# cloak.net
KiCad netlist of a schematic drawn in EAGLE
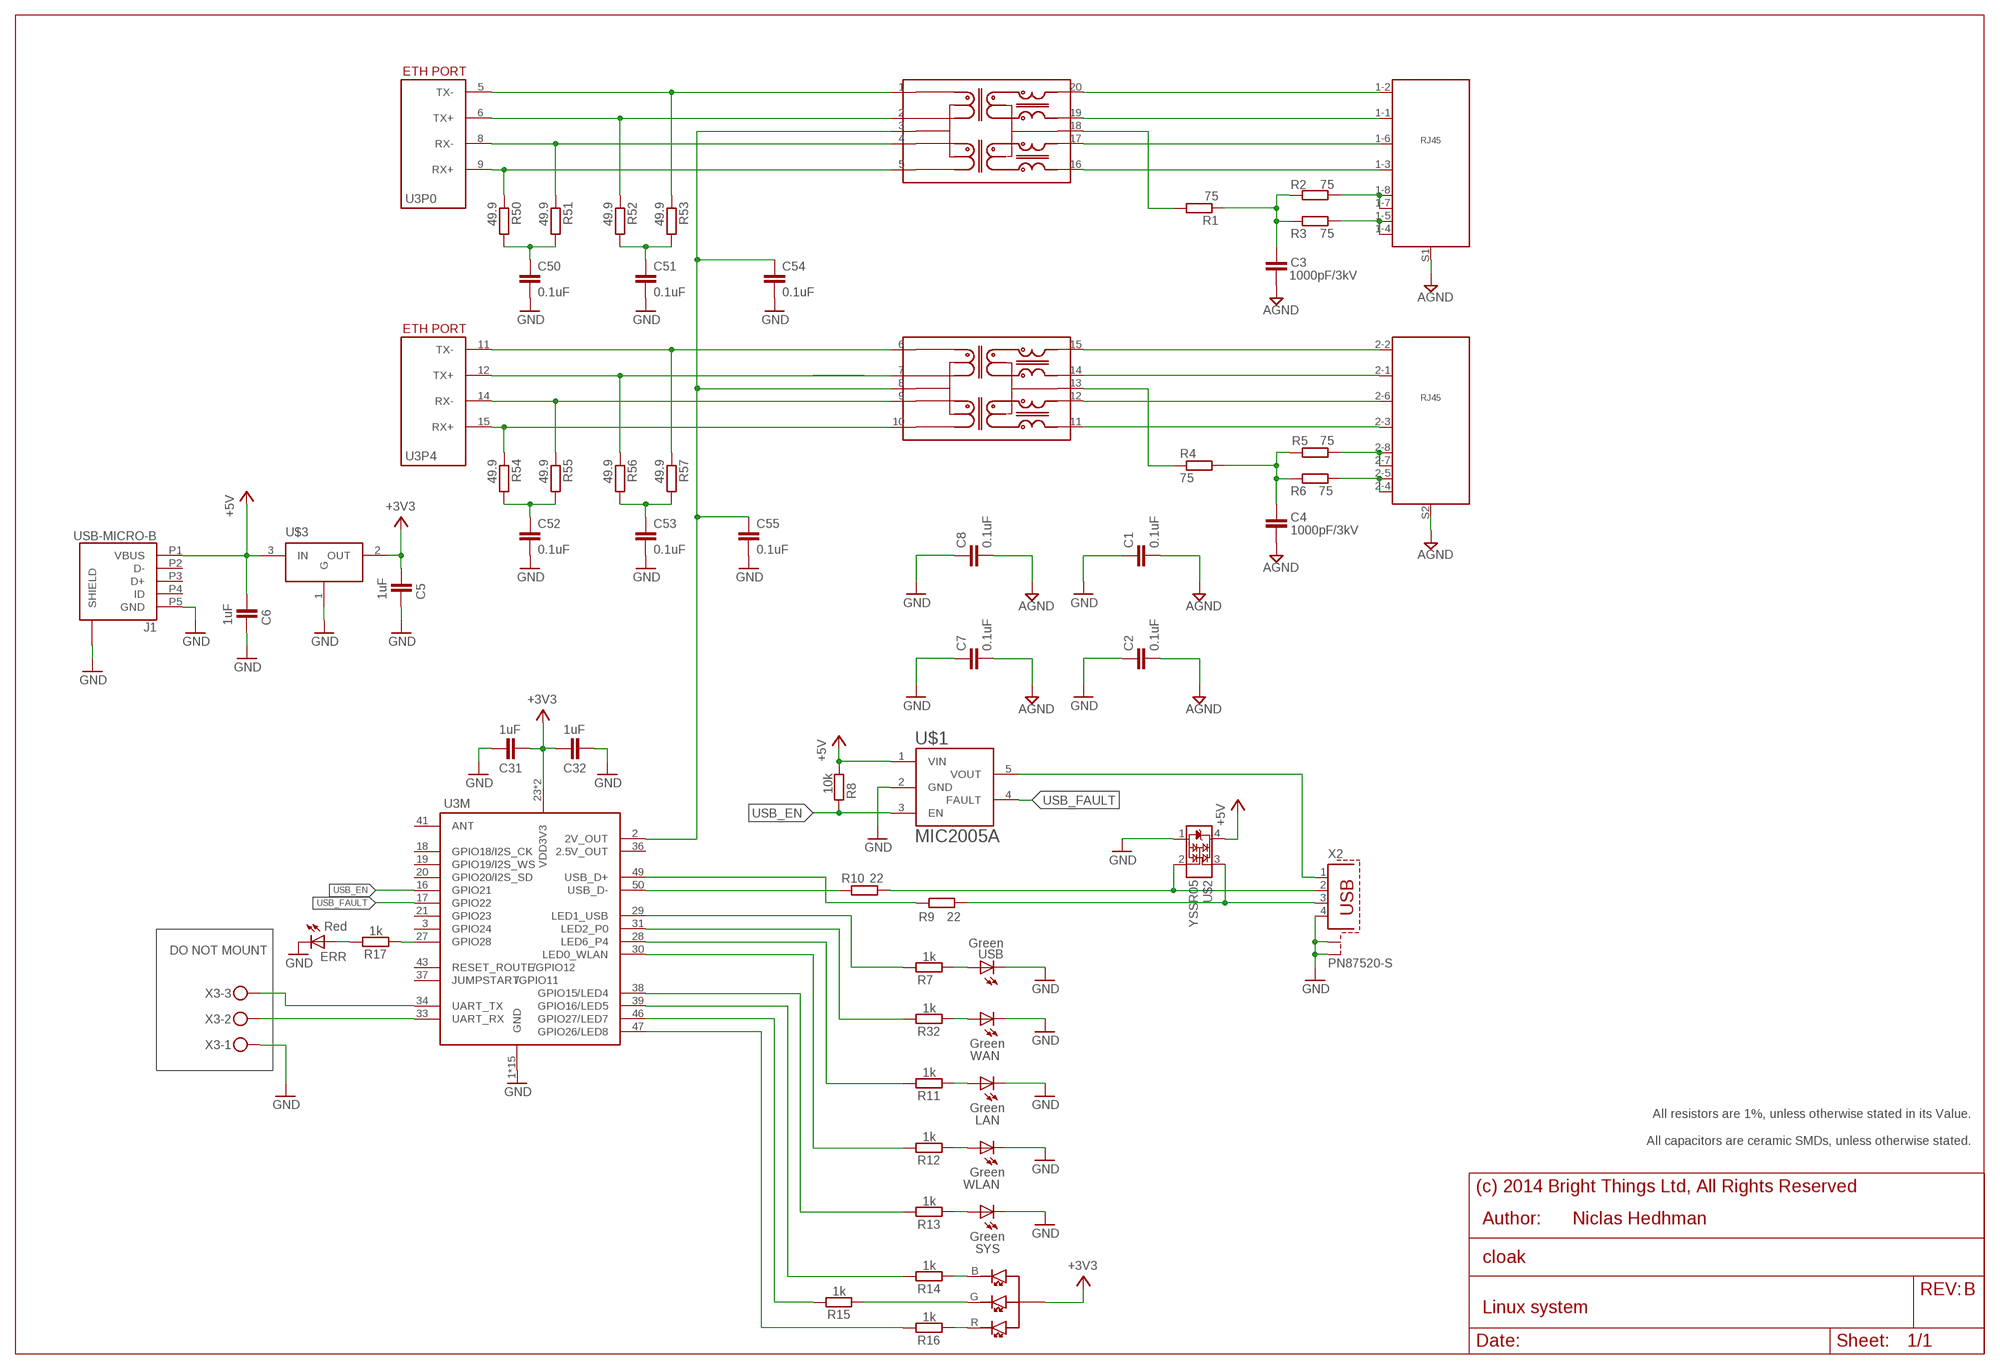
[diagram p0: schematic, sheet 1]

(export (version "E")
  (design (tool "Eeschema 10.0.6"))
  (components
    (comp (ref "C1")
      (value "0.1uF")
      (footprint "eagle-import:C0603")
      (fields (field (name "MANUFACTURER") "Kemet") (field (name "PARTNO") "C0603C104K5RAC7411"))
      (libsource (lib "eagle-import") (part "C-EUC0603"))
    )
    (comp (ref "C2")
      (value "0.1uF")
      (footprint "eagle-import:C0603")
      (fields (field (name "MANUFACTURER") "Kemet") (field (name "PARTNO") "C0603C104K5RAC7411"))
      (libsource (lib "eagle-import") (part "C-EUC0603"))
    )
    (comp (ref "C3")
      (value "1000pF/3kV")
      (footprint "eagle-import:C1808")
      (fields (field (name "MANUFACTURER") "Kemet") (field (name "PARTNO") "C1808C102KHRACTU"))
      (libsource (lib "eagle-import") (part "C-EUC1808"))
    )
    (comp (ref "C4")
      (value "1000pF/3kV")
      (footprint "eagle-import:C1808")
      (fields (field (name "MANUFACTURER") "Kemet") (field (name "PARTNO") "C1808C102KHRACTU"))
      (libsource (lib "eagle-import") (part "C-EUC1808"))
    )
    (comp (ref "C5")
      (value "1uF")
      (footprint "eagle-import:C0603")
      (fields (field (name "MF") "Kemet") (field (name "MPN") "C0603C105K8PACTU"))
      (libsource (lib "eagle-import") (part "C-EUC0603"))
    )
    (comp (ref "C6")
      (value "1uF")
      (footprint "eagle-import:C0603")
      (fields (field (name "MF") "Kemet") (field (name "MPN") "C0603C105K8PACTU"))
      (libsource (lib "eagle-import") (part "C-EUC0603"))
    )
    (comp (ref "C7")
      (value "0.1uF")
      (footprint "eagle-import:C0603")
      (fields (field (name "MANUFACTURER") "Kemet") (field (name "PARTNO") "C0603C104K5RAC7411"))
      (libsource (lib "eagle-import") (part "C-EUC0603"))
    )
    (comp (ref "C8")
      (value "0.1uF")
      (footprint "eagle-import:C0603")
      (fields (field (name "MANUFACTURER") "Kemet") (field (name "PARTNO") "C0603C104K5RAC7411"))
      (libsource (lib "eagle-import") (part "C-EUC0603"))
    )
    (comp (ref "C31")
      (value "1uF")
      (footprint "eagle-import:C0603")
      (fields (field (name "MF") "Kemet") (field (name "MPN") "C0603C105K8PACTU"))
      (libsource (lib "eagle-import") (part "C-EUC0603"))
    )
    (comp (ref "C32")
      (value "1uF")
      (footprint "eagle-import:C0603")
      (fields (field (name "MF") "Kemet") (field (name "MPN") "C0603C105K8PACTU"))
      (libsource (lib "eagle-import") (part "C-EUC0603"))
    )
    (comp (ref "C50")
      (value "0.1uF")
      (footprint "eagle-import:C0603")
      (fields (field (name "MF") "Kemet") (field (name "MPN") "C0603C104K5RAC7411"))
      (libsource (lib "eagle-import") (part "C-EUC0603"))
    )
    (comp (ref "C51")
      (value "0.1uF")
      (footprint "eagle-import:C0603")
      (fields (field (name "MF") "Kemet") (field (name "MPN") "C0603C104K5RAC7411"))
      (libsource (lib "eagle-import") (part "C-EUC0603"))
    )
    (comp (ref "C52")
      (value "0.1uF")
      (footprint "eagle-import:C0603")
      (fields (field (name "MF") "Kemet") (field (name "MPN") "C0603C104K5RAC7411"))
      (libsource (lib "eagle-import") (part "C-EUC0603"))
    )
    (comp (ref "C53")
      (value "0.1uF")
      (footprint "eagle-import:C0603")
      (fields (field (name "MF") "Kemet") (field (name "MPN") "C0603C104K5RAC7411"))
      (libsource (lib "eagle-import") (part "C-EUC0603"))
    )
    (comp (ref "C54")
      (value "0.1uF")
      (footprint "eagle-import:C0603")
      (fields (field (name "MF") "Kemet") (field (name "MPN") "C0603C104K5RAC7411"))
      (libsource (lib "eagle-import") (part "C-EUC0603"))
    )
    (comp (ref "C55")
      (value "0.1uF")
      (footprint "eagle-import:C0603")
      (fields (field (name "MF") "Kemet") (field (name "MPN") "C0603C104K5RAC7411"))
      (libsource (lib "eagle-import") (part "C-EUC0603"))
    )
    (comp (ref "CLOAK")
      (value "LTST-C19FD1WT")
      (footprint "eagle-import:LTST-C19FD1WT")
      (fields (field (name "MF") "Lite-On Inc"))
      (libsource (lib "eagle-import") (part "LTST-C19FD1WT"))
    )
    (comp (ref "ERR")
      (value "Red")
      (footprint "eagle-import:CHIP-LED0603")
      (fields (field (name "MF") "OSRAM Opto Semiconductors Inc") (field (name "MPN") "LG Q971-KN-1"))
      (libsource (lib "eagle-import") (part "LEDCHIP-LED0603"))
    )
    (comp (ref "J1")
      (value "USB-MICRO-B")
      (footprint "eagle-import:CON2_USB_MICRO_B_AT")
      (libsource (lib "eagle-import") (part "USB-MICRO-B"))
    )
    (comp (ref "LAN")
      (value "Green")
      (footprint "eagle-import:CHIP-LED0603")
      (fields (field (name "MF") "OSRAM Opto Semiconductors Inc") (field (name "MPN") "LG Q971-KN-1"))
      (libsource (lib "eagle-import") (part "LEDCHIP-LED0603"))
    )
    (comp (ref "P4")
      (value "ETHERNET_2PORT")
      (footprint "eagle-import:SJA-1X2")
      (libsource (lib "eagle-import") (part "ETHERNET_2PORT"))
    )
    (comp (ref "R1")
      (value "75")
      (footprint "eagle-import:R0805")
      (fields (field (name "MANUFACTURER") "Vishay Dale") (field (name "PARTNO") "CRCW060375R0FKEA"))
      (libsource (lib "eagle-import") (part "resistor_R-EU_R0805"))
    )
    (comp (ref "R2")
      (value "75")
      (footprint "eagle-import:R0805")
      (fields (field (name "MANUFACTURER") "Vishay Dale") (field (name "PARTNO") "CRCW060375R0FKEA"))
      (libsource (lib "eagle-import") (part "resistor_R-EU_R0805"))
    )
    (comp (ref "R3")
      (value "75")
      (footprint "eagle-import:R0805")
      (fields (field (name "MANUFACTURER") "Vishay Dale") (field (name "PARTNO") "CRCW060375R0FKEA"))
      (libsource (lib "eagle-import") (part "resistor_R-EU_R0805"))
    )
    (comp (ref "R4")
      (value "75")
      (footprint "eagle-import:R0805")
      (fields (field (name "MANUFACTURER") "Vishay Dale") (field (name "PARTNO") "CRCW060375R0FKEA"))
      (libsource (lib "eagle-import") (part "resistor_R-EU_R0805"))
    )
    (comp (ref "R5")
      (value "75")
      (footprint "eagle-import:R0805")
      (fields (field (name "MANUFACTURER") "Vishay Dale") (field (name "PARTNO") "CRCW060375R0FKEA"))
      (libsource (lib "eagle-import") (part "resistor_R-EU_R0805"))
    )
    (comp (ref "R6")
      (value "75")
      (footprint "eagle-import:R0805")
      (fields (field (name "MANUFACTURER") "Vishay Dale") (field (name "PARTNO") "CRCW060375R0FKEA"))
      (libsource (lib "eagle-import") (part "resistor_R-EU_R0805"))
    )
    (comp (ref "R7")
      (value "1k")
      (footprint "eagle-import:R0603")
      (fields (field (name "MF") "Vishay Dale") (field (name "MPN") "CRCW06031K0JNEA"))
      (libsource (lib "eagle-import") (part "R-EU_R0603"))
    )
    (comp (ref "R8")
      (value "10k")
      (footprint "eagle-import:R0603")
      (fields (field (name "MF") "Vishay Dale"))
      (libsource (lib "eagle-import") (part "R-EU_R0603"))
    )
    (comp (ref "R9")
      (value "22")
      (footprint "eagle-import:R0805")
      (fields (field (name "MANUFACTURER") "Vishay Dale") (field (name "PARTNO") "CRCW060322R0FKEA"))
      (libsource (lib "eagle-import") (part "resistor_R-EU_R0805"))
    )
    (comp (ref "R10")
      (value "22")
      (footprint "eagle-import:R0805")
      (fields (field (name "MANUFACTURER") "Vishay Dale") (field (name "PARTNO") "CRCW060322R0FKEA"))
      (libsource (lib "eagle-import") (part "resistor_R-EU_R0805"))
    )
    (comp (ref "R11")
      (value "1k")
      (footprint "eagle-import:R0603")
      (fields (field (name "MF") "Vishay Dale") (field (name "MPN") "CRCW06031K0JNEA"))
      (libsource (lib "eagle-import") (part "R-EU_R0603"))
    )
    (comp (ref "R12")
      (value "1k")
      (footprint "eagle-import:R0603")
      (fields (field (name "MF") "Vishay Dale") (field (name "MPN") "CRCW06031K0JNEA"))
      (libsource (lib "eagle-import") (part "R-EU_R0603"))
    )
    (comp (ref "R13")
      (value "1k")
      (footprint "eagle-import:R0603")
      (fields (field (name "MF") "Vishay Dale") (field (name "MPN") "CRCW06031K0JNEA"))
      (libsource (lib "eagle-import") (part "R-EU_R0603"))
    )
    (comp (ref "R14")
      (value "1k")
      (footprint "eagle-import:R0603")
      (fields (field (name "MF") "Vishay Dale") (field (name "MPN") "CRCW06031K0JNEA"))
      (libsource (lib "eagle-import") (part "R-EU_R0603"))
    )
    (comp (ref "R15")
      (value "1k")
      (footprint "eagle-import:R0603")
      (fields (field (name "MF") "Vishay Dale") (field (name "MPN") "CRCW06031K0JNEA"))
      (libsource (lib "eagle-import") (part "R-EU_R0603"))
    )
    (comp (ref "R16")
      (value "1k")
      (footprint "eagle-import:R0603")
      (fields (field (name "MF") "Vishay Dale") (field (name "MPN") "CRCW06031K0JNEA"))
      (libsource (lib "eagle-import") (part "R-EU_R0603"))
    )
    (comp (ref "R17")
      (value "1k")
      (footprint "eagle-import:R0603")
      (fields (field (name "MF") "Vishay Dale") (field (name "MPN") "CRCW06031K0JNEA"))
      (libsource (lib "eagle-import") (part "R-EU_R0603"))
    )
    (comp (ref "R32")
      (value "1k")
      (footprint "eagle-import:R0603")
      (fields (field (name "MF") "Vishay Dale") (field (name "MPN") "CRCW06031K0JNEA"))
      (libsource (lib "eagle-import") (part "R-EU_R0603"))
    )
    (comp (ref "R50")
      (value "49.9")
      (footprint "eagle-import:R0805")
      (fields (field (name "MF") "Vishay Dale") (field (name "MPN") "CRCW060349R9FKEA"))
      (libsource (lib "eagle-import") (part "resistor_R-EU_R0805"))
    )
    (comp (ref "R51")
      (value "49.9")
      (footprint "eagle-import:R0805")
      (fields (field (name "MF") "Vishay Dale") (field (name "MPN") "CRCW060349R9FKEA"))
      (libsource (lib "eagle-import") (part "resistor_R-EU_R0805"))
    )
    (comp (ref "R52")
      (value "49.9")
      (footprint "eagle-import:R0805")
      (fields (field (name "MF") "Vishay Dale") (field (name "MPN") "CRCW060349R9FKEA"))
      (libsource (lib "eagle-import") (part "resistor_R-EU_R0805"))
    )
    (comp (ref "R53")
      (value "49.9")
      (footprint "eagle-import:R0805")
      (fields (field (name "MF") "Vishay Dale") (field (name "MPN") "CRCW060349R9FKEA"))
      (libsource (lib "eagle-import") (part "resistor_R-EU_R0805"))
    )
    (comp (ref "R54")
      (value "49.9")
      (footprint "eagle-import:R0805")
      (fields (field (name "MF") "Vishay Dale") (field (name "MPN") "CRCW060349R9FKEA"))
      (libsource (lib "eagle-import") (part "resistor_R-EU_R0805"))
    )
    (comp (ref "R55")
      (value "49.9")
      (footprint "eagle-import:R0805")
      (fields (field (name "MF") "Vishay Dale") (field (name "MPN") "CRCW060349R9FKEA"))
      (libsource (lib "eagle-import") (part "resistor_R-EU_R0805"))
    )
    (comp (ref "R56")
      (value "49.9")
      (footprint "eagle-import:R0805")
      (fields (field (name "MF") "Vishay Dale") (field (name "MPN") "CRCW060349R9FKEA"))
      (libsource (lib "eagle-import") (part "resistor_R-EU_R0805"))
    )
    (comp (ref "R57")
      (value "49.9")
      (footprint "eagle-import:R0805")
      (fields (field (name "MF") "Vishay Dale") (field (name "MPN") "CRCW060349R9FKEA"))
      (libsource (lib "eagle-import") (part "resistor_R-EU_R0805"))
    )
    (comp (ref "SYS")
      (value "Green")
      (footprint "eagle-import:CHIP-LED0603")
      (fields (field (name "MF") "OSRAM Opto Semiconductors Inc") (field (name "MPN") "LG Q971-KN-1"))
      (libsource (lib "eagle-import") (part "LEDCHIP-LED0603"))
    )
    (comp (ref "TR1")
      (value "HST2038DR")
      (footprint "eagle-import:H2038")
      (fields (field (name "SUPPLIER") "Dragino"))
      (libsource (lib "eagle-import") (part "HST2038DR"))
    )
    (comp (ref "U$1")
      (value "MIC2005A")
      (footprint "eagle-import:SOT-23-5")
      (libsource (lib "eagle-import") (part "MIC2005A"))
    )
    (comp (ref "U$2")
      (value "YSSR05")
      (footprint "eagle-import:YSSR05")
      (libsource (lib "eagle-import") (part "YSSR05"))
    )
    (comp (ref "U$3")
      (value "LDO_REGL")
      (footprint "eagle-import:SOT23")
      (fields (field (name "MF") "Diodes Inc") (field (name "MPN") "AP2120N-3.3TRG1"))
      (libsource (lib "eagle-import") (part "LDO_REGL"))
    )
    (comp (ref "U3")
      (value "DRAGINO_HE")
      (footprint "eagle-import:DRAGINO_HE")
      (libsource (lib "eagle-import") (part "DRAGINO_HE"))
    )
    (comp (ref "USB")
      (value "Green")
      (footprint "eagle-import:CHIP-LED0603")
      (fields (field (name "MF") "OSRAM Opto Semiconductors Inc") (field (name "MPN") "LG Q971-KN-1"))
      (libsource (lib "eagle-import") (part "LEDCHIP-LED0603"))
    )
    (comp (ref "WAN")
      (value "Green")
      (footprint "eagle-import:CHIP-LED0603")
      (fields (field (name "MF") "OSRAM Opto Semiconductors Inc") (field (name "MPN") "LG Q971-KN-1"))
      (libsource (lib "eagle-import") (part "LEDCHIP-LED0603"))
    )
    (comp (ref "WLAN")
      (value "Green")
      (footprint "eagle-import:CHIP-LED0603")
      (fields (field (name "MF") "OSRAM Opto Semiconductors Inc") (field (name "MPN") "LG Q971-KN-1"))
      (libsource (lib "eagle-import") (part "LEDCHIP-LED0603"))
    )
    (comp (ref "X2")
      (value "PN87520-S")
      (footprint "eagle-import:PN87520-S")
      (libsource (lib "eagle-import") (part "PN87520-S"))
    )
    (comp (ref "X3")
      (value "MKDSN1,5/3-5,08")
      (footprint "eagle-import:MKDSN1,5_3-5,08")
      (fields (field (name "MPN") "SMKDSN1,5/3-5,08"))
      (libsource (lib "eagle-import") (part "MKDSN1,5/3-5,08"))
    )
  )
  (nets
    (net (code "1") (name "+3V3") (class "Default")
      (node (ref "C31") (pin "1") (pinfunction "1_1") (pintype "passive"))
      (node (ref "C32") (pin "1") (pinfunction "1_1") (pintype "passive"))
      (node (ref "C5") (pin "1") (pinfunction "1_1") (pintype "passive"))
      (node (ref "CLOAK") (pin "A") (pinfunction "A_A") (pintype "passive"))
      (node (ref "U$3") (pin "2") (pinfunction "OUT_2") (pintype "power_in"))
      (node (ref "U3") (pin "23") (pinfunction "VDD3V3_23") (pintype "power_in"))
      (node (ref "U3") (pin "24") (pinfunction "VDD3V3_24") (pintype "power_in"))
    )
    (net (code "2") (name "+5V") (class "Default")
      (node (ref "C6") (pin "1") (pinfunction "1_1") (pintype "passive"))
      (node (ref "J1") (pin "P1") (pinfunction "VBUS_P1") (pintype "power_in"))
      (node (ref "R8") (pin "2") (pinfunction "2_2") (pintype "passive"))
      (node (ref "U$1") (pin "1") (pinfunction "VIN_1") (pintype "power_in"))
      (node (ref "U$2") (pin "4") (pinfunction "+_4") (pintype "passive"))
      (node (ref "U$3") (pin "3") (pinfunction "IN_3") (pintype "power_in"))
    )
    (net (code "3") (name "/2.5V_OUT") (class "Default")
      (node (ref "U3") (pin "36") (pinfunction "2.5V_OUT_36") (pintype "power_in"))
    )
    (net (code "4") (name "AGND") (class "Default")
      (node (ref "C1") (pin "2") (pinfunction "2_2") (pintype "passive"))
      (node (ref "C2") (pin "2") (pinfunction "2_2") (pintype "passive"))
      (node (ref "C3") (pin "2") (pinfunction "2_2") (pintype "passive"))
      (node (ref "C4") (pin "2") (pinfunction "2_2") (pintype "passive"))
      (node (ref "C7") (pin "2") (pinfunction "2_2") (pintype "passive"))
      (node (ref "C8") (pin "2") (pinfunction "2_2") (pintype "passive"))
      (node (ref "P4") (pin "S1") (pinfunction "SHIELD_S1") (pintype "power_in"))
      (node (ref "P4") (pin "S2") (pinfunction "SHIELD_S2") (pintype "power_in"))
    )
    (net (code "5") (name "GND") (class "Default")
      (node (ref "C1") (pin "1") (pinfunction "1_1") (pintype "passive"))
      (node (ref "C2") (pin "1") (pinfunction "1_1") (pintype "passive"))
      (node (ref "C31") (pin "2") (pinfunction "2_2") (pintype "passive"))
      (node (ref "C32") (pin "2") (pinfunction "2_2") (pintype "passive"))
      (node (ref "C5") (pin "2") (pinfunction "2_2") (pintype "passive"))
      (node (ref "C50") (pin "2") (pinfunction "2_2") (pintype "passive"))
      (node (ref "C51") (pin "2") (pinfunction "2_2") (pintype "passive"))
      (node (ref "C52") (pin "2") (pinfunction "2_2") (pintype "passive"))
      (node (ref "C53") (pin "2") (pinfunction "2_2") (pintype "passive"))
      (node (ref "C54") (pin "2") (pinfunction "2_2") (pintype "passive"))
      (node (ref "C55") (pin "2") (pinfunction "2_2") (pintype "passive"))
      (node (ref "C6") (pin "2") (pinfunction "2_2") (pintype "passive"))
      (node (ref "C7") (pin "1") (pinfunction "1_1") (pintype "passive"))
      (node (ref "C8") (pin "1") (pinfunction "1_1") (pintype "passive"))
      (node (ref "ERR") (pin "C") (pinfunction "C_C") (pintype "passive"))
      (node (ref "J1") (pin "P5") (pinfunction "GND_P5") (pintype "passive"))
      (node (ref "J1") (pin "S1") (pinfunction "SHIELD_S1") (pintype "passive"))
      (node (ref "J1") (pin "S2") (pinfunction "SHIELD_S2") (pintype "passive"))
      (node (ref "J1") (pin "S3") (pinfunction "SHIELD_S3") (pintype "passive"))
      (node (ref "J1") (pin "S4") (pinfunction "SHIELD_S4") (pintype "passive"))
      (node (ref "J1") (pin "S5") (pinfunction "SHIELD_S5") (pintype "passive"))
      (node (ref "J1") (pin "S6") (pinfunction "SHIELD_S6") (pintype "passive"))
      (node (ref "LAN") (pin "C") (pinfunction "C_C") (pintype "passive"))
      (node (ref "SYS") (pin "C") (pinfunction "C_C") (pintype "passive"))
      (node (ref "U$1") (pin "2") (pinfunction "GND_2") (pintype "power_in"))
      (node (ref "U$2") (pin "1") (pinfunction "C_1") (pintype "passive"))
      (node (ref "U$3") (pin "1") (pinfunction "G_1") (pintype "power_in"))
      (node (ref "U3") (pin "1") (pinfunction "GND_1") (pintype "power_in"))
      (node (ref "U3") (pin "10") (pinfunction "GND_10") (pintype "power_in"))
      (node (ref "U3") (pin "13") (pinfunction "GND_13") (pintype "power_in"))
      (node (ref "U3") (pin "22") (pinfunction "GND_22") (pintype "power_in"))
      (node (ref "U3") (pin "25") (pinfunction "GND_25") (pintype "power_in"))
      (node (ref "U3") (pin "26") (pinfunction "GND_26") (pintype "power_in"))
      (node (ref "U3") (pin "32") (pinfunction "GND_32") (pintype "power_in"))
      (node (ref "U3") (pin "35") (pinfunction "GND_35") (pintype "power_in"))
      (node (ref "U3") (pin "4") (pinfunction "GND_4") (pintype "power_in"))
      (node (ref "U3") (pin "40") (pinfunction "GND_40") (pintype "power_in"))
      (node (ref "U3") (pin "42") (pinfunction "GND_42") (pintype "power_in"))
      (node (ref "U3") (pin "44") (pinfunction "GND_44") (pintype "power_in"))
      (node (ref "U3") (pin "45") (pinfunction "GND_45") (pintype "power_in"))
      (node (ref "U3") (pin "48") (pinfunction "GND_48") (pintype "power_in"))
      (node (ref "U3") (pin "7") (pinfunction "GND_7") (pintype "power_in"))
      (node (ref "USB") (pin "C") (pinfunction "C_C") (pintype "passive"))
      (node (ref "WAN") (pin "C") (pinfunction "C_C") (pintype "passive"))
      (node (ref "WLAN") (pin "C") (pinfunction "C_C") (pintype "passive"))
      (node (ref "X2") (pin "4") (pinfunction "4_4") (pintype "passive"))
      (node (ref "X2") (pin "S1") (pinfunction "S1_S1") (pintype "passive"))
      (node (ref "X2") (pin "S2") (pinfunction "S2_S2") (pintype "passive"))
      (node (ref "X3") (pin "1") (pinfunction "KL_1") (pintype "passive"))
    )
    (net (code "6") (name "Net-(C3-Pad1)") (class "Default")
      (node (ref "C3") (pin "1") (pinfunction "1_1") (pintype "passive"))
      (node (ref "R1") (pin "1") (pinfunction "1_1") (pintype "passive"))
      (node (ref "R2") (pin "2") (pinfunction "2_2") (pintype "passive"))
      (node (ref "R3") (pin "2") (pinfunction "2_2") (pintype "passive"))
    )
    (net (code "7") (name "Net-(C4-Pad1)") (class "Default")
      (node (ref "C4") (pin "1") (pinfunction "1_1") (pintype "passive"))
      (node (ref "R4") (pin "2") (pinfunction "2_2") (pintype "passive"))
      (node (ref "R5") (pin "2") (pinfunction "2_2") (pintype "passive"))
      (node (ref "R6") (pin "1") (pinfunction "1_1") (pintype "passive"))
    )
    (net (code "8") (name "Net-(C50-Pad1)") (class "Default")
      (node (ref "C50") (pin "1") (pinfunction "1_1") (pintype "passive"))
      (node (ref "R50") (pin "2") (pinfunction "2_2") (pintype "passive"))
      (node (ref "R51") (pin "2") (pinfunction "2_2") (pintype "passive"))
    )
    (net (code "9") (name "Net-(C51-Pad1)") (class "Default")
      (node (ref "C51") (pin "1") (pinfunction "1_1") (pintype "passive"))
      (node (ref "R52") (pin "2") (pinfunction "2_2") (pintype "passive"))
      (node (ref "R53") (pin "2") (pinfunction "2_2") (pintype "passive"))
    )
    (net (code "10") (name "Net-(C52-Pad1)") (class "Default")
      (node (ref "C52") (pin "1") (pinfunction "1_1") (pintype "passive"))
      (node (ref "R54") (pin "2") (pinfunction "2_2") (pintype "passive"))
      (node (ref "R55") (pin "2") (pinfunction "2_2") (pintype "passive"))
    )
    (net (code "11") (name "Net-(C53-Pad1)") (class "Default")
      (node (ref "C53") (pin "1") (pinfunction "1_1") (pintype "passive"))
      (node (ref "R56") (pin "2") (pinfunction "2_2") (pintype "passive"))
      (node (ref "R57") (pin "2") (pinfunction "2_2") (pintype "passive"))
    )
    (net (code "12") (name "Net-(CLOAK-PadB)") (class "Default")
      (node (ref "CLOAK") (pin "B") (pinfunction "B_B") (pintype "passive"))
      (node (ref "R14") (pin "2") (pinfunction "2_2") (pintype "passive"))
    )
    (net (code "13") (name "Net-(CLOAK-PadG)") (class "Default")
      (node (ref "CLOAK") (pin "G") (pinfunction "G_G") (pintype "passive"))
      (node (ref "R15") (pin "2") (pinfunction "2_2") (pintype "passive"))
    )
    (net (code "14") (name "Net-(CLOAK-PadR)") (class "Default")
      (node (ref "CLOAK") (pin "R") (pinfunction "R_R") (pintype "passive"))
      (node (ref "R16") (pin "2") (pinfunction "2_2") (pintype "passive"))
    )
    (net (code "15") (name "Net-(ERR-PadA)") (class "Default")
      (node (ref "ERR") (pin "A") (pinfunction "A_A") (pintype "passive"))
      (node (ref "R17") (pin "1") (pinfunction "1_1") (pintype "passive"))
    )
    (net (code "16") (name "Net-(LAN-PadA)") (class "Default")
      (node (ref "LAN") (pin "A") (pinfunction "A_A") (pintype "passive"))
      (node (ref "R11") (pin "2") (pinfunction "2_2") (pintype "passive"))
    )
    (net (code "17") (name "Net-(P4A-1)") (class "Default")
      (node (ref "P4") (pin "1-1") (pinfunction "1_1-1") (pintype "passive"))
      (node (ref "TR1") (pin "19") (pinfunction "TX-_19") (pintype "passive"))
    )
    (net (code "18") (name "Net-(P4A-2)") (class "Default")
      (node (ref "P4") (pin "1-2") (pinfunction "2_1-2") (pintype "passive"))
      (node (ref "TR1") (pin "20") (pinfunction "TX+_20") (pintype "passive"))
    )
    (net (code "19") (name "Net-(P4A-3)") (class "Default")
      (node (ref "P4") (pin "1-3") (pinfunction "3_1-3") (pintype "passive"))
      (node (ref "TR1") (pin "16") (pinfunction "RX-_16") (pintype "passive"))
    )
    (net (code "20") (name "Net-(P4A-4)") (class "Default")
      (node (ref "P4") (pin "1-4") (pinfunction "4_1-4") (pintype "passive"))
      (node (ref "P4") (pin "1-5") (pinfunction "5_1-5") (pintype "passive"))
      (node (ref "R3") (pin "1") (pinfunction "1_1") (pintype "passive"))
    )
    (net (code "21") (name "Net-(P4A-6)") (class "Default")
      (node (ref "P4") (pin "1-6") (pinfunction "6_1-6") (pintype "passive"))
      (node (ref "TR1") (pin "17") (pinfunction "RX+_17") (pintype "passive"))
    )
    (net (code "22") (name "Net-(P4A-7)") (class "Default")
      (node (ref "P4") (pin "1-7") (pinfunction "7_1-7") (pintype "passive"))
      (node (ref "P4") (pin "1-8") (pinfunction "8_1-8") (pintype "passive"))
      (node (ref "R2") (pin "1") (pinfunction "1_1") (pintype "passive"))
    )
    (net (code "23") (name "Net-(P4B-1)") (class "Default")
      (node (ref "P4") (pin "2-1") (pinfunction "1_2-1") (pintype "passive"))
      (node (ref "TR1") (pin "14") (pinfunction "TX-_14") (pintype "passive"))
    )
    (net (code "24") (name "Net-(P4B-2)") (class "Default")
      (node (ref "P4") (pin "2-2") (pinfunction "2_2-2") (pintype "passive"))
      (node (ref "TR1") (pin "15") (pinfunction "TX+_15") (pintype "passive"))
    )
    (net (code "25") (name "Net-(P4B-3)") (class "Default")
      (node (ref "P4") (pin "2-3") (pinfunction "3_2-3") (pintype "passive"))
      (node (ref "TR1") (pin "11") (pinfunction "RX-_11") (pintype "passive"))
    )
    (net (code "26") (name "Net-(P4B-4)") (class "Default")
      (node (ref "P4") (pin "2-4") (pinfunction "4_2-4") (pintype "passive"))
      (node (ref "P4") (pin "2-5") (pinfunction "5_2-5") (pintype "passive"))
      (node (ref "R6") (pin "2") (pinfunction "2_2") (pintype "passive"))
    )
    (net (code "27") (name "Net-(P4B-6)") (class "Default")
      (node (ref "P4") (pin "2-6") (pinfunction "6_2-6") (pintype "passive"))
      (node (ref "TR1") (pin "12") (pinfunction "RX+_12") (pintype "passive"))
    )
    (net (code "28") (name "Net-(P4B-7)") (class "Default")
      (node (ref "P4") (pin "2-7") (pinfunction "7_2-7") (pintype "passive"))
      (node (ref "P4") (pin "2-8") (pinfunction "8_2-8") (pintype "passive"))
      (node (ref "R5") (pin "1") (pinfunction "1_1") (pintype "passive"))
    )
    (net (code "29") (name "Net-(R7-Pad2)") (class "Default")
      (node (ref "R7") (pin "2") (pinfunction "2_2") (pintype "passive"))
      (node (ref "USB") (pin "A") (pinfunction "A_A") (pintype "passive"))
    )
    (net (code "30") (name "Net-(R12-Pad2)") (class "Default")
      (node (ref "R12") (pin "2") (pinfunction "2_2") (pintype "passive"))
      (node (ref "WLAN") (pin "A") (pinfunction "A_A") (pintype "passive"))
    )
    (net (code "31") (name "Net-(R13-Pad2)") (class "Default")
      (node (ref "R13") (pin "2") (pinfunction "2_2") (pintype "passive"))
      (node (ref "SYS") (pin "A") (pinfunction "A_A") (pintype "passive"))
    )
    (net (code "32") (name "Net-(R32-Pad2)") (class "Default")
      (node (ref "R32") (pin "2") (pinfunction "2_2") (pintype "passive"))
      (node (ref "WAN") (pin "A") (pinfunction "A_A") (pintype "passive"))
    )
    (net (code "33") (name "Net-(TR1A-CT1)") (class "Default")
      (node (ref "C54") (pin "1") (pinfunction "1_1") (pintype "passive"))
      (node (ref "C55") (pin "1") (pinfunction "1_1") (pintype "passive"))
      (node (ref "TR1") (pin "3") (pinfunction "CT1_3") (pintype "passive"))
      (node (ref "TR1") (pin "8") (pinfunction "CT1_8") (pintype "passive"))
      (node (ref "U3") (pin "2") (pinfunction "2V_OUT_2") (pintype "power_in"))
    )
    (net (code "34") (name "Net-(TR1A-CT2)") (class "Default")
      (node (ref "R1") (pin "2") (pinfunction "2_2") (pintype "passive"))
      (node (ref "TR1") (pin "18") (pinfunction "CT2_18") (pintype "passive"))
    )
    (net (code "35") (name "Net-(TR1A-RD+)") (class "Default")
      (node (ref "R51") (pin "1") (pinfunction "1_1") (pintype "passive"))
      (node (ref "TR1") (pin "4") (pinfunction "RD+_4") (pintype "passive"))
      (node (ref "U3") (pin "8") (pinfunction "RX-_8") (pintype "bidirectional"))
    )
    (net (code "36") (name "Net-(TR1A-RD-)") (class "Default")
      (node (ref "R50") (pin "1") (pinfunction "1_1") (pintype "passive"))
      (node (ref "TR1") (pin "5") (pinfunction "RD-_5") (pintype "passive"))
      (node (ref "U3") (pin "9") (pinfunction "RX+_9") (pintype "bidirectional"))
    )
    (net (code "37") (name "Net-(TR1A-TD+)") (class "Default")
      (node (ref "R53") (pin "1") (pinfunction "1_1") (pintype "passive"))
      (node (ref "TR1") (pin "1") (pinfunction "TD+_1") (pintype "passive"))
      (node (ref "U3") (pin "5") (pinfunction "TX-_5") (pintype "bidirectional"))
    )
    (net (code "38") (name "Net-(TR1A-TD-)") (class "Default")
      (node (ref "R52") (pin "1") (pinfunction "1_1") (pintype "passive"))
      (node (ref "TR1") (pin "2") (pinfunction "TD-_2") (pintype "passive"))
      (node (ref "U3") (pin "6") (pinfunction "TX+_6") (pintype "bidirectional"))
    )
    (net (code "39") (name "Net-(TR1B-CT2)") (class "Default")
      (node (ref "R4") (pin "1") (pinfunction "1_1") (pintype "passive"))
      (node (ref "TR1") (pin "13") (pinfunction "CT2_13") (pintype "passive"))
    )
    (net (code "40") (name "Net-(TR1B-RD+)") (class "Default")
      (node (ref "R55") (pin "1") (pinfunction "1_1") (pintype "passive"))
      (node (ref "TR1") (pin "9") (pinfunction "RD+_9") (pintype "passive"))
      (node (ref "U3") (pin "14") (pinfunction "RX-_14") (pintype "bidirectional"))
    )
    (net (code "41") (name "Net-(TR1B-RD-)") (class "Default")
      (node (ref "R54") (pin "1") (pinfunction "1_1") (pintype "passive"))
      (node (ref "TR1") (pin "10") (pinfunction "RD-_10") (pintype "passive"))
      (node (ref "U3") (pin "15") (pinfunction "RX+_15") (pintype "bidirectional"))
    )
    (net (code "42") (name "Net-(TR1B-TD+)") (class "Default")
      (node (ref "R57") (pin "1") (pinfunction "1_1") (pintype "passive"))
      (node (ref "TR1") (pin "6") (pinfunction "TD+_6") (pintype "passive"))
      (node (ref "U3") (pin "11") (pinfunction "TX-_11") (pintype "bidirectional"))
    )
    (net (code "43") (name "Net-(TR1B-TD-)") (class "Default")
      (node (ref "R56") (pin "1") (pinfunction "1_1") (pintype "passive"))
      (node (ref "TR1") (pin "7") (pinfunction "TD-_7") (pintype "passive"))
      (node (ref "U3") (pin "12") (pinfunction "TX+_12") (pintype "bidirectional"))
    )
    (net (code "44") (name "Net-(U$1-VOUT)") (class "Default")
      (node (ref "U$1") (pin "5") (pinfunction "VOUT_5") (pintype "power_in"))
      (node (ref "X2") (pin "1") (pinfunction "1_1") (pintype "passive"))
    )
    (net (code "45") (name "Net-(U$2-A)") (class "Default")
      (node (ref "R9") (pin "1") (pinfunction "1_1") (pintype "passive"))
      (node (ref "U$2") (pin "3") (pinfunction "A_3") (pintype "passive"))
      (node (ref "X2") (pin "3") (pinfunction "3_3") (pintype "passive"))
    )
    (net (code "46") (name "Net-(U$2-B)") (class "Default")
      (node (ref "R10") (pin "1") (pinfunction "1_1") (pintype "passive"))
      (node (ref "U$2") (pin "2") (pinfunction "B_2") (pintype "passive"))
      (node (ref "X2") (pin "2") (pinfunction "2_2") (pintype "passive"))
    )
    (net (code "47") (name "Net-(U3A-GPIO28)") (class "Default")
      (node (ref "R17") (pin "2") (pinfunction "2_2") (pintype "passive"))
      (node (ref "U3") (pin "27") (pinfunction "GPIO28_27") (pintype "bidirectional"))
    )
    (net (code "48") (name "Net-(U3A-LED0_WLAN)") (class "Default")
      (node (ref "R12") (pin "1") (pinfunction "1_1") (pintype "passive"))
      (node (ref "U3") (pin "30") (pinfunction "LED0_WLAN_30") (pintype "bidirectional"))
    )
    (net (code "49") (name "Net-(U3A-LED1_USB)") (class "Default")
      (node (ref "R7") (pin "1") (pinfunction "1_1") (pintype "passive"))
      (node (ref "U3") (pin "29") (pinfunction "LED1_USB_29") (pintype "bidirectional"))
    )
    (net (code "50") (name "Net-(U3A-LED2_P0)") (class "Default")
      (node (ref "R32") (pin "1") (pinfunction "1_1") (pintype "passive"))
      (node (ref "U3") (pin "31") (pinfunction "LED2_P0_31") (pintype "bidirectional"))
    )
    (net (code "51") (name "Net-(U3A-LED4)") (class "Default")
      (node (ref "R13") (pin "1") (pinfunction "1_1") (pintype "passive"))
      (node (ref "U3") (pin "38") (pinfunction "LED4_38") (pintype "bidirectional"))
    )
    (net (code "52") (name "Net-(U3A-LED5)") (class "Default")
      (node (ref "R14") (pin "1") (pinfunction "1_1") (pintype "passive"))
      (node (ref "U3") (pin "39") (pinfunction "LED5_39") (pintype "bidirectional"))
    )
    (net (code "53") (name "Net-(U3A-LED6_P4)") (class "Default")
      (node (ref "R11") (pin "1") (pinfunction "1_1") (pintype "passive"))
      (node (ref "U3") (pin "28") (pinfunction "LED6_P4_28") (pintype "bidirectional"))
    )
    (net (code "54") (name "Net-(U3A-LED7)") (class "Default")
      (node (ref "R15") (pin "1") (pinfunction "1_1") (pintype "passive"))
      (node (ref "U3") (pin "46") (pinfunction "LED7_46") (pintype "bidirectional"))
    )
    (net (code "55") (name "Net-(U3A-LED8)") (class "Default")
      (node (ref "R16") (pin "1") (pinfunction "1_1") (pintype "passive"))
      (node (ref "U3") (pin "47") (pinfunction "LED8_47") (pintype "bidirectional"))
    )
    (net (code "56") (name "Net-(U3A-UART_RX)") (class "Default")
      (node (ref "U3") (pin "33") (pinfunction "UART_RX_33") (pintype "bidirectional"))
      (node (ref "X3") (pin "2") (pinfunction "KL_2") (pintype "passive"))
    )
    (net (code "57") (name "Net-(U3A-UART_TX)") (class "Default")
      (node (ref "U3") (pin "34") (pinfunction "UART_TX_34") (pintype "bidirectional"))
      (node (ref "X3") (pin "3") (pinfunction "KL_3") (pintype "passive"))
    )
    (net (code "58") (name "Net-(U3A-USB_D+)") (class "Default")
      (node (ref "R9") (pin "2") (pinfunction "2_2") (pintype "passive"))
      (node (ref "U3") (pin "49") (pinfunction "USB_D+_49") (pintype "bidirectional"))
    )
    (net (code "59") (name "Net-(U3A-USB_D-)") (class "Default")
      (node (ref "R10") (pin "2") (pinfunction "2_2") (pintype "passive"))
      (node (ref "U3") (pin "50") (pinfunction "USB_D-_50") (pintype "bidirectional"))
    )
    (net (code "60") (name "USB_EN") (class "Default")
      (node (ref "R8") (pin "1") (pinfunction "1_1") (pintype "passive"))
      (node (ref "U$1") (pin "3") (pinfunction "EN_3") (pintype "input"))
      (node (ref "U3") (pin "16") (pinfunction "GPIO21_16") (pintype "bidirectional"))
    )
    (net (code "61") (name "USB_FAULT") (class "Default")
      (node (ref "U$1") (pin "4") (pinfunction "FAULT_4") (pintype "output"))
      (node (ref "U3") (pin "17") (pinfunction "GPIO22_17") (pintype "bidirectional"))
    )
    (net (code "62") (name "unconnected-(J1-D+-PadP3)") (class "Default")
      (node (ref "J1") (pin "P3") (pinfunction "D+_P3") (pintype "bidirectional"))
    )
    (net (code "63") (name "unconnected-(J1-D--PadP2)") (class "Default")
      (node (ref "J1") (pin "P2") (pinfunction "D-_P2") (pintype "bidirectional"))
    )
    (net (code "64") (name "unconnected-(J1-ID-PadP4)") (class "Default")
      (node (ref "J1") (pin "P4") (pinfunction "ID_P4") (pintype "bidirectional"))
    )
    (net (code "65") (name "unconnected-(U3A-ANT-Pad41)") (class "Default")
      (node (ref "U3") (pin "41") (pinfunction "ANT_41") (pintype "passive"))
    )
    (net (code "66") (name "unconnected-(U3A-GPIO18-Pad18)") (class "Default")
      (node (ref "U3") (pin "18") (pinfunction "GPIO18_18") (pintype "bidirectional"))
    )
    (net (code "67") (name "unconnected-(U3A-GPIO19-Pad19)") (class "Default")
      (node (ref "U3") (pin "19") (pinfunction "GPIO19_19") (pintype "bidirectional"))
    )
    (net (code "68") (name "unconnected-(U3A-GPIO20-Pad20)") (class "Default")
      (node (ref "U3") (pin "20") (pinfunction "GPIO20_20") (pintype "bidirectional"))
    )
    (net (code "69") (name "unconnected-(U3A-GPIO23-Pad21)") (class "Default")
      (node (ref "U3") (pin "21") (pinfunction "GPIO23_21") (pintype "bidirectional"))
    )
    (net (code "70") (name "unconnected-(U3A-GPIO24-Pad3)") (class "Default")
      (node (ref "U3") (pin "3") (pinfunction "GPIO24_3") (pintype "bidirectional"))
    )
    (net (code "71") (name "unconnected-(U3A-JUMPSTART-Pad37)") (class "Default")
      (node (ref "U3") (pin "37") (pinfunction "JUMPSTART_37") (pintype "bidirectional"))
    )
    (net (code "72") (name "unconnected-(U3A-RESET_ROUTE-Pad43)") (class "Default")
      (node (ref "U3") (pin "43") (pinfunction "RESET_ROUTE_43") (pintype "bidirectional"))
    )
  )
)
